# TempCtrl.net
KiCad netlist of a schematic drawn in Altium Designer
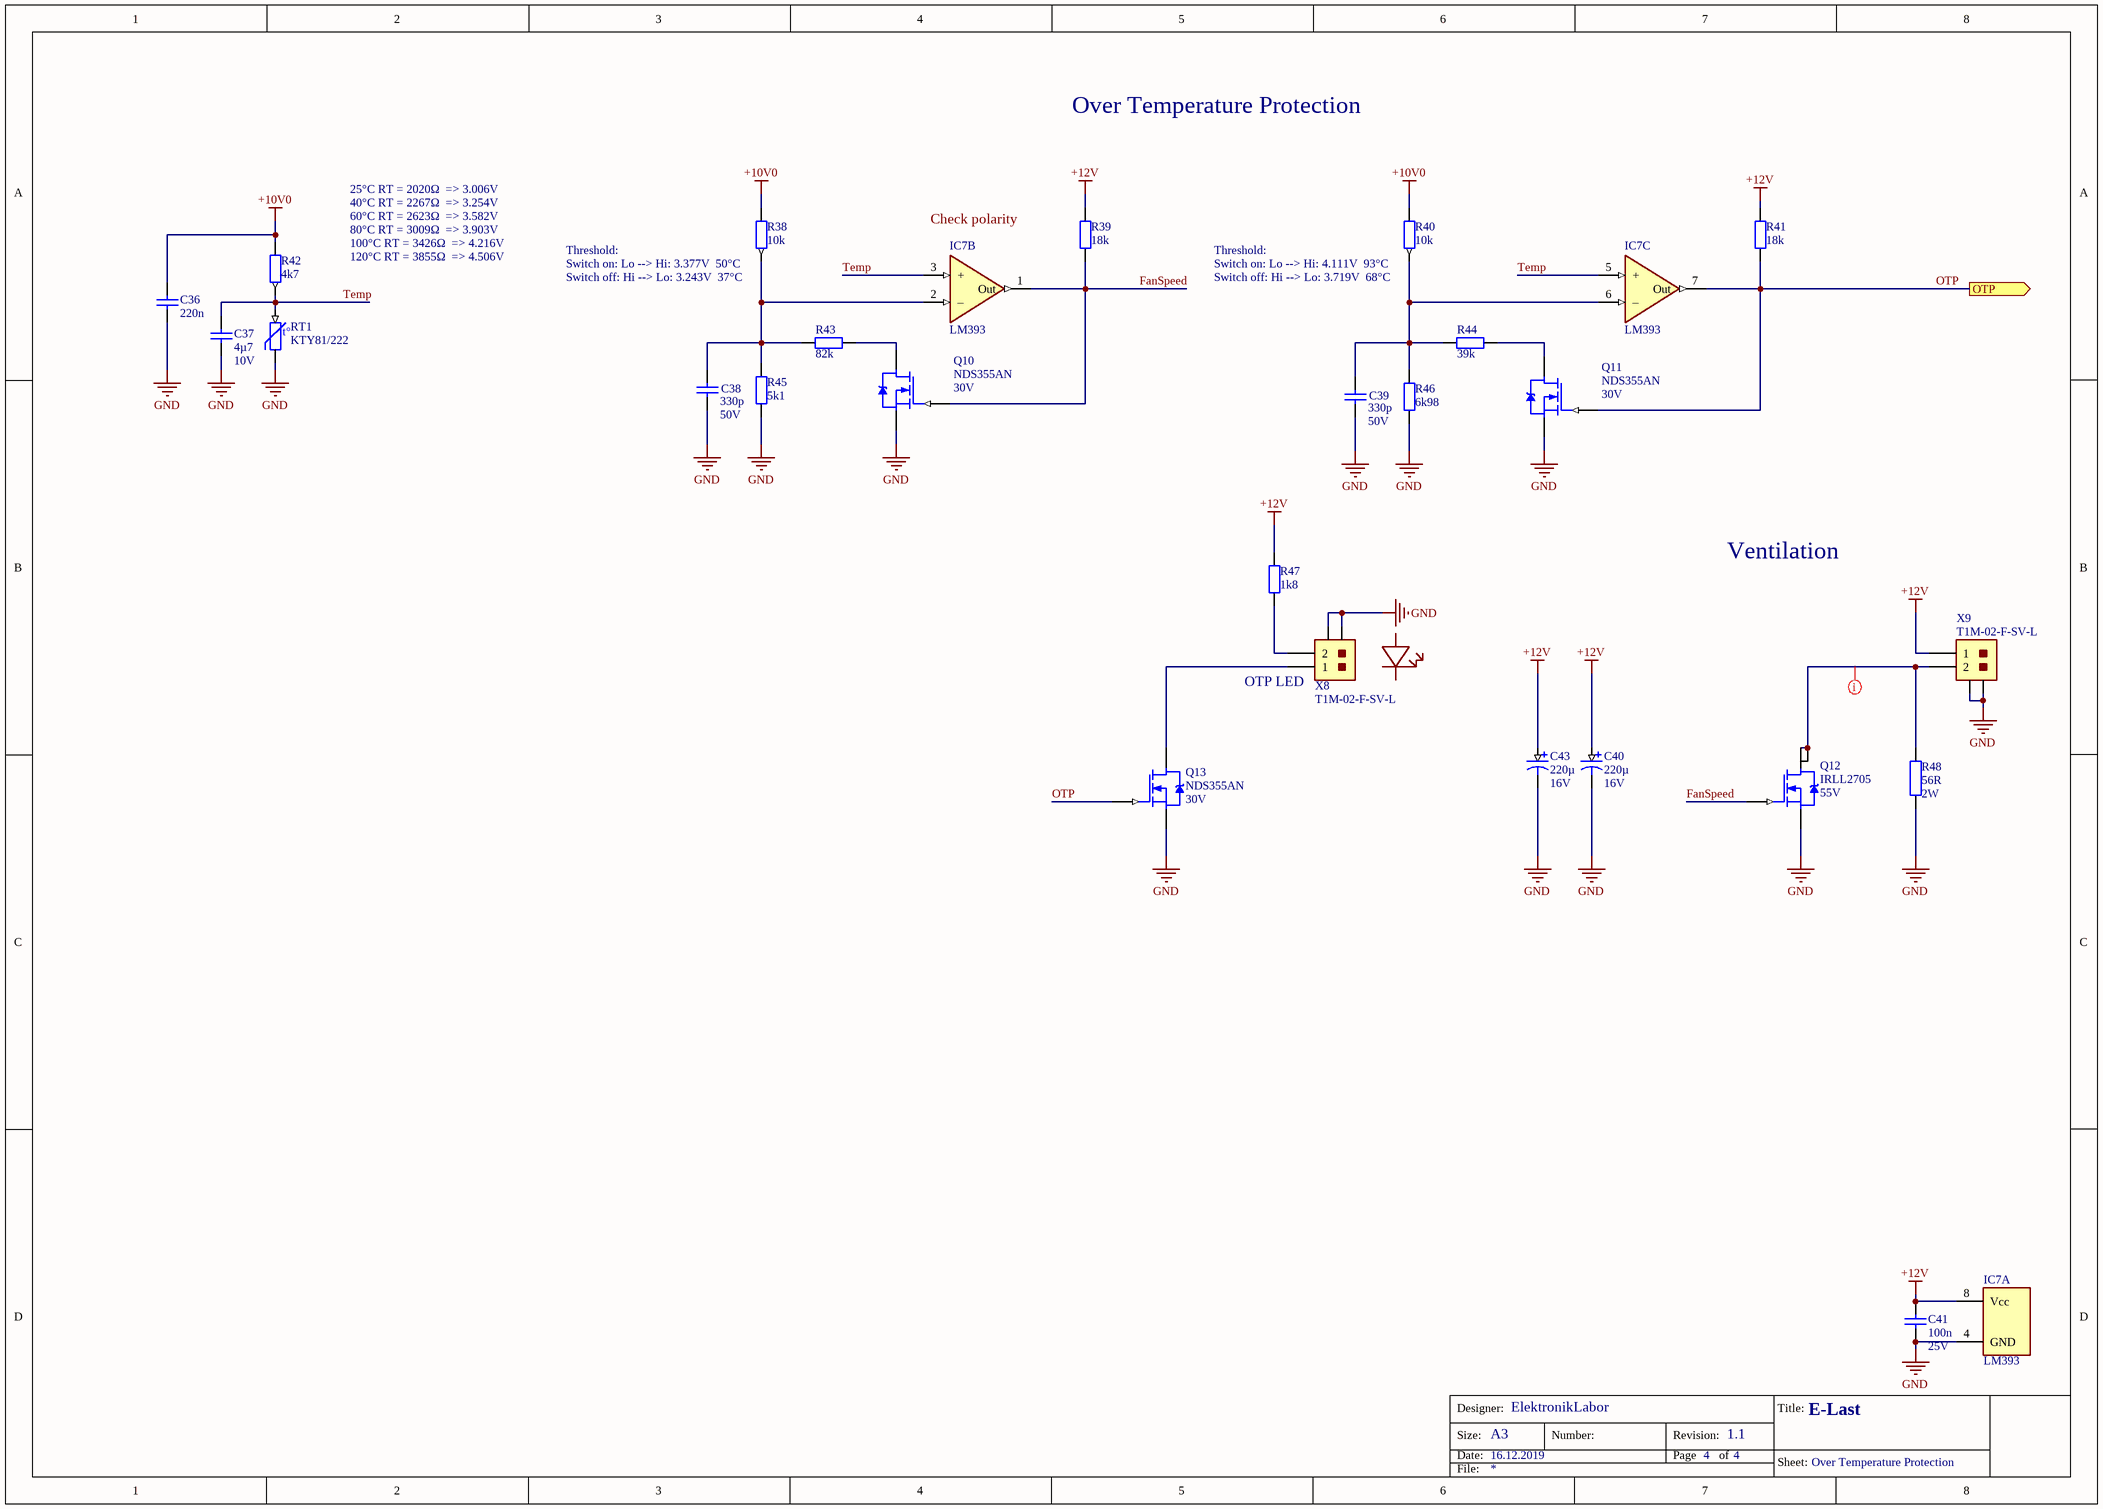
[diagram p0: TempCtrl.SchDoc]

(export (version "E")
  (design (tool "Eeschema 10.0.6"))
  (components
    (comp (ref "C36")
      (value "220n")
      (footprint "C_0805")
      (description "Cap Ceramic 0805 220n 50V")
      (fields (field (name "MANUFACTURER") "generic") (field (name "VOLTAGE") "50V"))
      (libsource (lib "SchLibrary") (part "C-Cer 0805 220n"))
    )
    (comp (ref "C37")
      (value "4µ7")
      (footprint "C_0805")
      (description "Cap Ceramic 0805 4µ7 10V")
      (fields (field (name "MANUFACTURER") "generic") (field (name "VOLTAGE") "10V"))
      (libsource (lib "CustomLib") (part "C-Cer 0805 4µ7"))
    )
    (comp (ref "C38")
      (value "330p")
      (footprint "C_0805")
      (description "Cap Ceramic 0805 330p 50V")
      (fields (field (name "MANUFACTURER") "generic") (field (name "VOLTAGE") "50V"))
      (libsource (lib "CustomLib") (part "C-Cer 0805 330p"))
    )
    (comp (ref "C39")
      (value "330p")
      (footprint "C_0805")
      (description "Cap Ceramic 0805 330p 50V")
      (fields (field (name "MANUFACTURER") "generic") (field (name "VOLTAGE") "50V"))
      (libsource (lib "CustomLib") (part "C-Cer 0805 330p"))
    )
    (comp (ref "C40")
      (value "220µ")
      (footprint "Cap Tantal E (2917)")
      (description "Cap Tantal 220µ 16V SMD")
      (fields
        (field (name "MANUFACTURER") "AVX")
        (field (name "PARTNUMBER") "TPSE227*016#0100")
        (field (name "VOLTAGE") "16V")
        (field (name "COMPONENTLINK1URL") "G:\\Daten\\Datenblätter\\Kondensatoren\\AVX_Tantal_TPS.pdf")
      )
      (libsource (lib "CustomLib") (part "Cap Tantal 220µ"))
    )
    (comp (ref "C41")
      (value "100n")
      (footprint "C_0805")
      (description "Cap Ceramic 0805 100n 25V")
      (fields (field (name "MANUFACTURER") "generic") (field (name "VOLTAGE") "25V"))
      (libsource (lib "SchLibrary") (part "C-Cer 0805 100n"))
    )
    (comp (ref "C43")
      (value "220µ")
      (footprint "Cap Tantal E (2917)")
      (description "Cap Tantal 220µ 16V SMD")
      (fields
        (field (name "MANUFACTURER") "AVX")
        (field (name "PARTNUMBER") "TPSE227*016#0100")
        (field (name "VOLTAGE") "16V")
        (field (name "COMPONENTLINK1URL") "G:\\Daten\\Datenblätter\\Kondensatoren\\AVX_Tantal_TPS.pdf")
      )
      (libsource (lib "CustomLib") (part "Cap Tantal 220µ"))
    )
    (comp (ref "IC7")
      (value "LM393")
      (footprint "SOIC8_N")
      (description "Comparator LM393DT 2x")
      (fields
        (field (name "MANUFACTURER") "ST")
        (field (name "PARTNUMBER") "LM393DT")
        (field (name "COMPONENTLINK1URL") "G:\\Daten\\Datenblätter\\Komparatoren\\ST_LM393.pdf")
      )
      (libsource (lib "SchLibrary") (part "LM393DT"))
    )
    (comp (ref "Q10")
      (value "NDS355AN")
      (footprint "SOT23_N - n-MOS")
      (description "Transistor n-MOS SOT-23 30V Vgs=20V")
      (fields
        (field (name "MANUFACTURER") "ON Semiconductor")
        (field (name "VOLTAGE") "30V")
        (field (name "COMPONENTLINK1URL") "G:\\Daten\\Datenblätter\\Transistoren\\nMOS_NDS355AN.pdf")
      )
      (libsource (lib "CustomLib") (part "Transistor n-MOS NDS355AN"))
    )
    (comp (ref "Q11")
      (value "NDS355AN")
      (footprint "SOT23_N - n-MOS")
      (description "Transistor n-MOS SOT-23 30V Vgs=20V")
      (fields
        (field (name "MANUFACTURER") "ON Semiconductor")
        (field (name "VOLTAGE") "30V")
        (field (name "COMPONENTLINK1URL") "G:\\Daten\\Datenblätter\\Transistoren\\nMOS_NDS355AN.pdf")
      )
      (libsource (lib "CustomLib") (part "Transistor n-MOS NDS355AN"))
    )
    (comp (ref "Q12")
      (value "IRLL2705")
      (footprint "SOT-223")
      (description "Transistor n-MOS SOT-223 55V Vgs=16V")
      (fields
        (field (name "MANUFACTURER") "International Rectifier")
        (field (name "PARTNUMBER") "IRLL2705PbF")
        (field (name "VOLTAGE") "55V")
        (field (name "COMPONENTLINK1URL") "G:\\Daten\\Datenblätter\\Transistoren\\nMOS_IRLL2705.pdf")
      )
      (libsource (lib "SchLibrary") (part "Transistor n-MOS IRLL2705"))
    )
    (comp (ref "Q13")
      (value "NDS355AN")
      (footprint "SOT23_N - n-MOS")
      (description "Transistor n-MOS SOT-23 30V Vgs=20V")
      (fields
        (field (name "MANUFACTURER") "ON Semiconductor")
        (field (name "VOLTAGE") "30V")
        (field (name "COMPONENTLINK1URL") "G:\\Daten\\Datenblätter\\Transistoren\\nMOS_NDS355AN.pdf")
      )
      (libsource (lib "CustomLib") (part "Transistor n-MOS NDS355AN"))
    )
    (comp (ref "R38")
      (value "10k")
      (footprint "Res 0805")
      (description "Resistor 0805 10k")
      (fields (field (name "MANUFACTURER") "generic") (field (name "POWER") "0.125W"))
      (libsource (lib "SchLibrary") (part "Res 0805 10k"))
    )
    (comp (ref "R39")
      (value "18k")
      (footprint "Res 0805")
      (description "Resistor 0805 18k")
      (fields (field (name "MANUFACTURER") "generic") (field (name "POWER") "0.125W"))
      (libsource (lib "SchLibrary") (part "Res 0805 18k"))
    )
    (comp (ref "R40")
      (value "10k")
      (footprint "Res 0805")
      (description "Resistor 0805 10k")
      (fields (field (name "MANUFACTURER") "generic") (field (name "POWER") "0.125W"))
      (libsource (lib "SchLibrary") (part "Res 0805 10k"))
    )
    (comp (ref "R41")
      (value "18k")
      (footprint "Res 0805")
      (description "Resistor 0805 18k")
      (fields (field (name "MANUFACTURER") "generic") (field (name "POWER") "0.125W"))
      (libsource (lib "SchLibrary") (part "Res 0805 18k"))
    )
    (comp (ref "R42")
      (value "4k7")
      (footprint "Res 0805")
      (description "Resistor 0805 4k7")
      (fields (field (name "MANUFACTURER") "generic") (field (name "POWER") "0.125W"))
      (libsource (lib "SchLibrary") (part "Res 0805 4k7"))
    )
    (comp (ref "R43")
      (value "82k")
      (footprint "Res 0805")
      (description "Resistor 0805 82k")
      (fields (field (name "MANUFACTURER") "generic") (field (name "POWER") "0.125W"))
      (libsource (lib "CustomLib") (part "Res 0805 82k"))
    )
    (comp (ref "R44")
      (value "39k")
      (footprint "Res 0805")
      (description "Resistor 0805 39k")
      (fields (field (name "MANUFACTURER") "generic") (field (name "POWER") "0.125W"))
      (libsource (lib "CustomLib") (part "Res 0805 39k"))
    )
    (comp (ref "R45")
      (value "5k1")
      (footprint "Res 0805")
      (description "Resistor 0805 5k1")
      (fields (field (name "MANUFACTURER") "generic") (field (name "POWER") "0.125W"))
      (libsource (lib "SchLibrary") (part "Res 0805 5k1"))
    )
    (comp (ref "R46")
      (value "6k98")
      (footprint "Res 0805")
      (description "Resistor 0805 6k98")
      (fields (field (name "MANUFACTURER") "generic") (field (name "POWER") "0.125W"))
      (libsource (lib "CustomLib") (part "Res 0805 6k98"))
    )
    (comp (ref "R47")
      (value "1k8")
      (footprint "Res 0805")
      (description "Resistor 0805 1k8")
      (fields (field (name "MANUFACTURER") "generic") (field (name "POWER") "0.125W"))
      (libsource (lib "SchLibrary") (part "Res 0805 1k8"))
    )
    (comp (ref "R48")
      (value "56R")
      (footprint "RES PO593-0 vert")
      (description "Resistor 56R 2W THT")
      (fields
        (field (name "MANUFACTURER") "VITROHM")
        (field (name "PARTNUMBER") "PO593-0 5 T 56R")
        (field (name "POWER") "2W")
        (field (name "COMPONENTLINK1URL") "G:\\Daten\\Datenblätter\\Widerstände\\VITROHM_series_PO.pdf")
      )
      (libsource (lib "CustomLib") (part "Res Power 56R"))
    )
    (comp (ref "RT1")
      (value "KTY81/222")
      (footprint "TO-92-2")
      (description "Sensor Temp 2k TO92-2")
      (fields
        (field (name "MANUFACTURER") "NXP")
        (field (name "COMPONENTLINK1URL") "G:\\Daten\\Datenblätter\\Sensoren\\KTY81.pdf")
      )
      (libsource (lib "SchLibrary") (part "KTY81/222"))
    )
    (comp (ref "X8")
      (value "T1M-02-F-SV-L")
      (footprint "T1M-02-XX-S-V")
      (description "Connector, Male, Vertical, 2-Pin, 1mm, SMD")
      (fields
        (field (name "MANUFACTURER") "SAMTEC")
        (field (name "MATINGPARTNUMBER") "S1SS-02-L")
        (field (name "COMPONENTLINK1URL") "G:\\Daten\\Datenblätter\\Steckverbinder\\T1M-Single-Row.pdf")
      )
      (libsource (lib "") (part "Con Male 2-Pin_1"))
    )
    (comp (ref "X9")
      (value "T1M-02-F-SV-L")
      (footprint "T1M-02-XX-S-V")
      (description "Connector, Male, Vertical, 2-Pin, 1mm, SMD")
      (fields
        (field (name "MANUFACTURER") "SAMTEC")
        (field (name "MATINGPARTNUMBER") "S1SS-02-L")
        (field (name "COMPONENTLINK1URL") "G:\\Daten\\Datenblätter\\Steckverbinder\\T1M-Single-Row.pdf")
      )
      (libsource (lib "SchLibrary") (part "Con Male 2-Pin"))
    )
  )
  (nets
    (net (code "1") (name "+10V0") (class "Default")
      (node (ref "C36") (pin "1") (pinfunction "1_1") (pintype "passive"))
      (node (ref "R38") (pin "1") (pinfunction "1_1") (pintype "passive"))
      (node (ref "R40") (pin "1") (pinfunction "1_1") (pintype "passive"))
      (node (ref "R42") (pin "1") (pinfunction "1_1") (pintype "passive"))
    )
    (net (code "2") (name "+12V") (class "Default")
      (node (ref "C40") (pin "1") (pinfunction "1_1") (pintype "input"))
      (node (ref "C41") (pin "1") (pinfunction "1_1") (pintype "passive"))
      (node (ref "C43") (pin "1") (pinfunction "1_1") (pintype "input"))
      (node (ref "IC7") (pin "8") (pinfunction "Vcc_8") (pintype "power_in"))
      (node (ref "R39") (pin "1") (pinfunction "1_1") (pintype "passive"))
      (node (ref "R41") (pin "1") (pinfunction "1_1") (pintype "passive"))
      (node (ref "R47") (pin "1") (pinfunction "1_1") (pintype "passive"))
      (node (ref "X9") (pin "1") (pinfunction "1_1") (pintype "passive"))
    )
    (net (code "3") (name "/FanSpeed") (class "Default")
      (node (ref "IC7") (pin "1") (pinfunction "Out_1") (pintype "output"))
      (node (ref "Q10") (pin "1") (pinfunction "G_1") (pintype "input"))
      (node (ref "Q12") (pin "1") (pinfunction "G_1") (pintype "input"))
      (node (ref "R39") (pin "2") (pinfunction "2_2") (pintype "passive"))
    )
    (net (code "4") (name "/OTP") (class "Default")
      (node (ref "IC7") (pin "7") (pinfunction "Out_7") (pintype "output"))
      (node (ref "Q11") (pin "1") (pinfunction "G_1") (pintype "input"))
      (node (ref "Q13") (pin "1") (pinfunction "G_1") (pintype "input"))
      (node (ref "R41") (pin "2") (pinfunction "2_2") (pintype "passive"))
    )
    (net (code "5") (name "/Temp") (class "Default")
      (node (ref "C37") (pin "1") (pinfunction "1_1") (pintype "passive"))
      (node (ref "IC7") (pin "3") (pinfunction "+_3") (pintype "input"))
      (node (ref "IC7") (pin "5") (pinfunction "+_5") (pintype "input"))
      (node (ref "R42") (pin "2") (pinfunction "2_2") (pintype "output"))
      (node (ref "RT1") (pin "2") (pinfunction "2_2") (pintype "input"))
    )
    (net (code "6") (name "GND") (class "Default")
      (node (ref "C36") (pin "2") (pinfunction "2_2") (pintype "passive"))
      (node (ref "C37") (pin "2") (pinfunction "2_2") (pintype "passive"))
      (node (ref "C38") (pin "2") (pinfunction "2_2") (pintype "passive"))
      (node (ref "C39") (pin "2") (pinfunction "2_2") (pintype "passive"))
      (node (ref "C40") (pin "2") (pinfunction "2_2") (pintype "power_in"))
      (node (ref "C41") (pin "2") (pinfunction "2_2") (pintype "passive"))
      (node (ref "C43") (pin "2") (pinfunction "2_2") (pintype "power_in"))
      (node (ref "IC7") (pin "4") (pinfunction "GND_4") (pintype "passive"))
      (node (ref "Q10") (pin "2") (pinfunction "S_2") (pintype "passive"))
      (node (ref "Q11") (pin "2") (pinfunction "S_2") (pintype "passive"))
      (node (ref "Q12") (pin "3") (pinfunction "S_3") (pintype "passive"))
      (node (ref "Q13") (pin "2") (pinfunction "S_2") (pintype "passive"))
      (node (ref "R45") (pin "2") (pinfunction "2_2") (pintype "passive"))
      (node (ref "R46") (pin "2") (pinfunction "2_2") (pintype "passive"))
      (node (ref "R48") (pin "2") (pinfunction "2_2") (pintype "passive"))
      (node (ref "RT1") (pin "1") (pinfunction "1_1") (pintype "power_in"))
      (node (ref "X8") (pin "3") (pinfunction "CASE_3") (pintype "passive"))
      (node (ref "X8") (pin "4") (pinfunction "CASE_4") (pintype "passive"))
      (node (ref "X9") (pin "3") (pinfunction "CASE_3") (pintype "passive"))
      (node (ref "X9") (pin "4") (pinfunction "CASE_4") (pintype "passive"))
    )
    (net (code "7") (name "Net-(IC7B-–)") (class "Default")
      (node (ref "C38") (pin "1") (pinfunction "1_1") (pintype "passive"))
      (node (ref "IC7") (pin "2") (pinfunction "–_2") (pintype "input"))
      (node (ref "R38") (pin "2") (pinfunction "2_2") (pintype "output"))
      (node (ref "R43") (pin "1") (pinfunction "1_1") (pintype "passive"))
      (node (ref "R45") (pin "1") (pinfunction "1_1") (pintype "passive"))
    )
    (net (code "8") (name "Net-(IC7C-–)") (class "Default")
      (node (ref "C39") (pin "1") (pinfunction "1_1") (pintype "passive"))
      (node (ref "IC7") (pin "6") (pinfunction "–_6") (pintype "input"))
      (node (ref "R40") (pin "2") (pinfunction "2_2") (pintype "output"))
      (node (ref "R44") (pin "1") (pinfunction "1_1") (pintype "passive"))
      (node (ref "R46") (pin "1") (pinfunction "1_1") (pintype "passive"))
    )
    (net (code "9") (name "Net-(Q10-D)") (class "Default")
      (node (ref "Q10") (pin "3") (pinfunction "D_3") (pintype "passive"))
      (node (ref "R43") (pin "2") (pinfunction "2_2") (pintype "passive"))
    )
    (net (code "10") (name "Net-(Q11-D)") (class "Default")
      (node (ref "Q11") (pin "3") (pinfunction "D_3") (pintype "passive"))
      (node (ref "R44") (pin "2") (pinfunction "2_2") (pintype "passive"))
    )
    (net (code "11") (name "Net-(Q12-D-Pad2)") (class "Default")
      (node (ref "Q12") (pin "2") (pinfunction "D_2") (pintype "passive"))
      (node (ref "Q12") (pin "4") (pinfunction "D_4") (pintype "passive"))
      (node (ref "R48") (pin "1") (pinfunction "1_1") (pintype "passive"))
      (node (ref "X9") (pin "2") (pinfunction "2_2") (pintype "passive"))
    )
    (net (code "12") (name "Net-(Q13-D)") (class "Default")
      (node (ref "Q13") (pin "3") (pinfunction "D_3") (pintype "passive"))
      (node (ref "X8") (pin "1") (pinfunction "1_1") (pintype "passive"))
    )
    (net (code "13") (name "Net-(R47-Pad2)") (class "Default")
      (node (ref "R47") (pin "2") (pinfunction "2_2") (pintype "passive"))
      (node (ref "X8") (pin "2") (pinfunction "2_2") (pintype "passive"))
    )
  )
)
